# S7CAS-PLEIADES-CARTE-MERE_P02_FLASH.net
KiCad netlist of a schematic drawn in Altium Designer
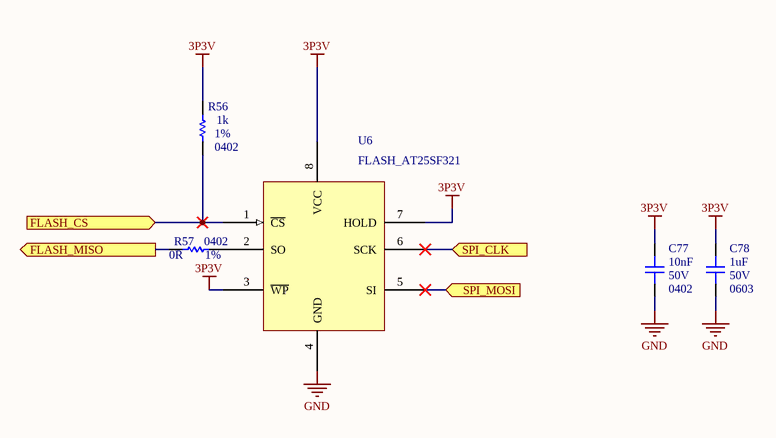
[diagram p0: S7CAS-PLEIADES-CARTE-MERE_P02_FLASH.SchDoc]

(export (version "E")
  (design (tool "Eeschema 10.0.6"))
  (components
    (comp (ref "C77")
      (value "10nF")
      (footprint "CAP_0402")
      (description "CAP - 0603")
      (fields
        (field (name "VOLTAGE") "50V")
        (field (name "PACKAGE") "0402")
        (field (name "CREATEDBY") "Jonathan Bouchard")
      )
      (libsource (lib "S7CAS_Lib2019_REV1_00") (part "CAP - 0603"))
    )
    (comp (ref "C78")
      (value "1uF")
      (footprint "CAP_0603")
      (description "CAP - 0603")
      (fields
        (field (name "VOLTAGE") "50V")
        (field (name "PACKAGE") "0603")
        (field (name "CREATEDBY") "Jonathan Bouchard")
      )
      (libsource (lib "S7CAS_Lib2019_REV1_00") (part "CAP - 0603"))
    )
    (comp (ref "R56")
      (value "1k")
      (footprint "RES_0402")
      (description "RES - 0402")
      (fields
        (field (name "VOLTAGE") "50V")
        (field (name "POWER") "1/16W")
        (field (name "PACKAGE") "0402")
        (field (name "PRECISION") "1%")
        (field (name "CREATEDBY") "Jonathan Bouchard")
      )
      (libsource (lib "S7CAS_Lib2019_REV1_00") (part "RES - 0402"))
    )
    (comp (ref "R57")
      (value "0R")
      (footprint "RES_0402")
      (description "RES - 0402")
      (fields
        (field (name "VOLTAGE") "50V")
        (field (name "POWER") "1/16W")
        (field (name "PACKAGE") "0402")
        (field (name "PRECISION") "1%")
        (field (name "CREATEDBY") "Jonathan Bouchard")
      )
      (libsource (lib "S7CAS_Lib2019_REV1_00") (part "RES - 0402"))
    )
    (comp (ref "U6")
      (value "FLASH_AT25SF321")
      (footprint "8-SOIC")
      (libsource (lib "lib_Emile") (part "FLASH_AT25SF321"))
    )
  )
  (nets
    (net (code "1") (name "/FLASH_CS") (class "Default")
      (node (ref "R56") (pin "1") (pinfunction "1_1") (pintype "passive"))
      (node (ref "U6") (pin "1") (pinfunction "~{CS}_1") (pintype "input"))
    )
    (net (code "2") (name "/FLASH_MISO") (class "Default")
      (node (ref "R57") (pin "2") (pinfunction "2_2") (pintype "passive"))
    )
    (net (code "3") (name "/SPI_CLK") (class "Default")
      (node (ref "U6") (pin "6") (pinfunction "SCK_6") (pintype "passive+no_connect"))
    )
    (net (code "4") (name "/SPI_MOSI") (class "Default")
      (node (ref "U6") (pin "5") (pinfunction "SI_5") (pintype "passive+no_connect"))
    )
    (net (code "5") (name "3P3V") (class "Default")
      (node (ref "C77") (pin "2") (pinfunction "2_2") (pintype "passive"))
      (node (ref "C78") (pin "2") (pinfunction "2_2") (pintype "passive"))
      (node (ref "R56") (pin "2") (pinfunction "2_2") (pintype "passive"))
      (node (ref "U6") (pin "3") (pinfunction "~{WP}_3") (pintype "power_in"))
      (node (ref "U6") (pin "7") (pinfunction "HOLD_7") (pintype "passive"))
      (node (ref "U6") (pin "8") (pinfunction "VCC_8") (pintype "power_in"))
    )
    (net (code "6") (name "GND") (class "Default")
      (node (ref "C77") (pin "1") (pinfunction "1_1") (pintype "passive"))
      (node (ref "C78") (pin "1") (pinfunction "1_1") (pintype "passive"))
      (node (ref "U6") (pin "4") (pinfunction "GND_4") (pintype "power_in"))
    )
    (net (code "7") (name "Net-(U6-SO)") (class "Default")
      (node (ref "R57") (pin "1") (pinfunction "1_1") (pintype "passive"))
      (node (ref "U6") (pin "2") (pinfunction "SO_2") (pintype "power_in"))
    )
  )
)
